# RFID-Reader.net
KiCad netlist of a schematic drawn in Altium Designer
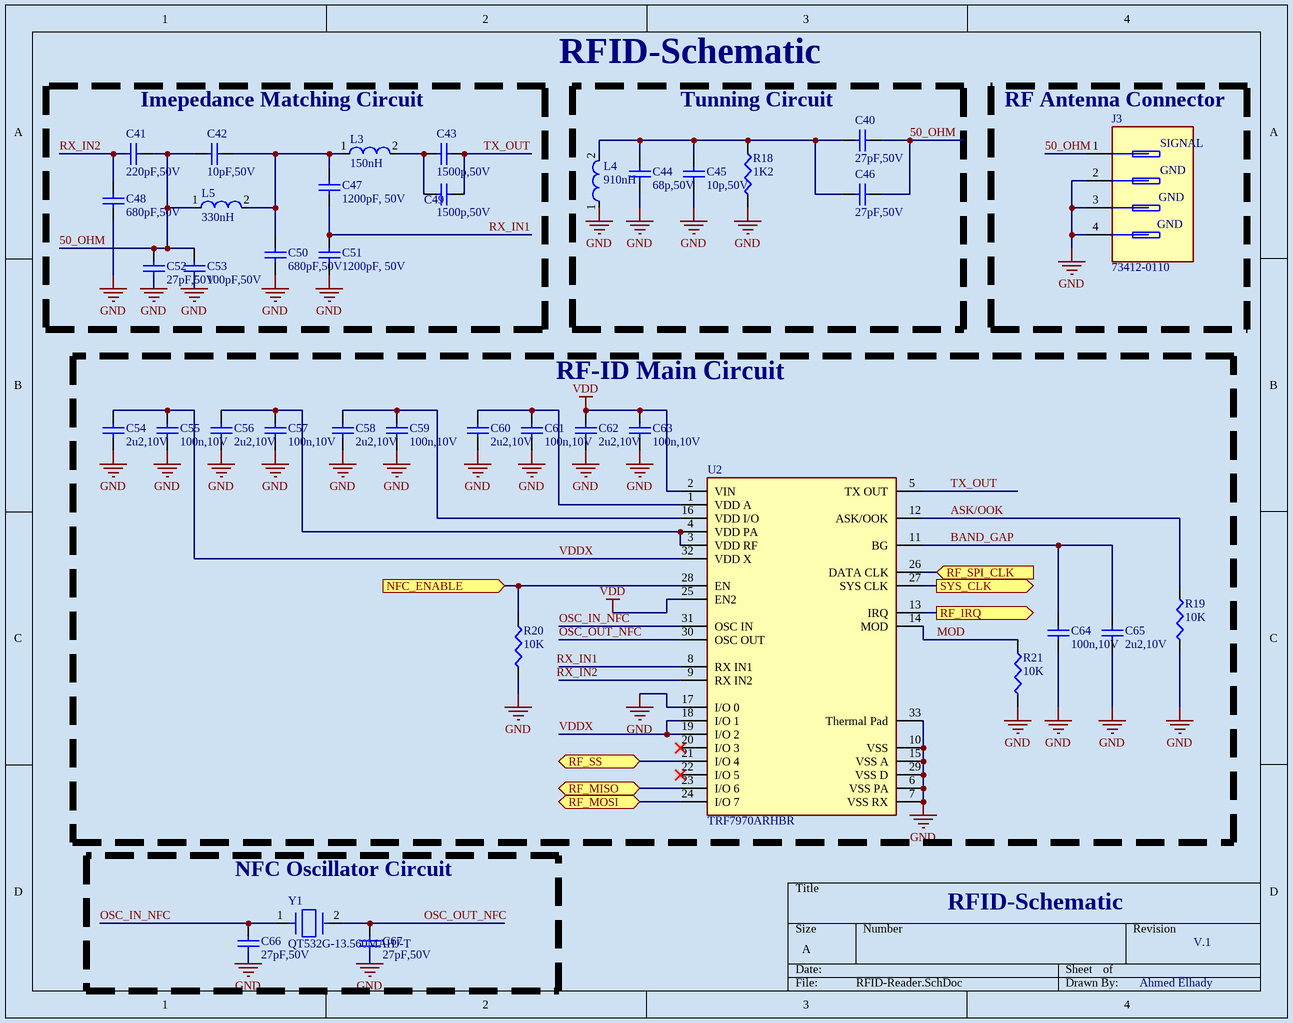
[diagram p0: RFID-Reader.SchDoc]

(export (version "E")
  (design (tool "Eeschema 10.0.6"))
  (components
    (comp (ref "C40")
      (value "27pF,50V")
      (footprint "C0402-27pf-50V")
      (description "27 pF ±5% 50V Ceramic Capacitor C0G, NP0 0402 (1005 Metric)")
      (fields
        (field (name "MANUFACTURER") "Yageo Group")
        (field (name "MANUFACTURER PART NUMBER") "CC0402JRNPO9BN270")
      )
      (libsource (lib "Sch for NFC") (part "CC0402JRNPO9BN270"))
    )
    (comp (ref "C41")
      (value "220pF,50V")
      (footprint "220pf-50v-0402-yageo-CAPC1005X55N")
      (description "220 pF ±5% 25V Ceramic Capacitor C0G, NP0 0402 (1005 Metric)")
      (fields
        (field (name "MANUFACTURER") "Yageo Group")
        (field (name "MANUFACTURER PART NUMBER") "CC0402JRNPO8BN221")
      )
      (libsource (lib "Sch for NFC") (part "CC0402JRNPO8BN221"))
    )
    (comp (ref "C42")
      (value "10pF,50V")
      (footprint "YAGEO_10pf-50v-CC0402JRNPO9BN100_0")
      (description "10 pF ±5% 50V Ceramic Capacitor C0G, NP0 0402 (1005 Metric)")
      (fields
        (field (name "MANUFACTURER") "Yageo Group")
        (field (name "MANUFACTURER PART NUMBER") "CC0402JRNPO9BN100")
      )
      (libsource (lib "Sch for NFC") (part "CC0402JRNPO9BN100"))
    )
    (comp (ref "C43")
      (value "1500p,50V")
      (footprint "C0402-1500pF-Murata_GRM15_MFG")
      (description "1500 pF ±10% 50V Ceramic Capacitor X7R 0402 (1005 Metric)")
      (fields
        (field (name "MANUFACTURER") "Murata")
        (field (name "MANUFACTURER PART NUMBER") "GRM155R71H152KA01D")
      )
      (libsource (lib "Sch for NFC") (part "GRM155R71H152KA01D"))
    )
    (comp (ref "C44")
      (value "68p,50V")
      (footprint "TDK_C1005-68pf-50v")
      (description "68 pF ±5% 50V Ceramic Capacitor C0G, NP0 0402 (1005 Metric)")
      (fields
        (field (name "MANUFACTURER") "TDK")
        (field (name "MANUFACTURER PART NUMBER") "C1005C0G1H680J050BA")
      )
      (libsource (lib "Sch for NFC") (part "C1005C0G1H680J050BA"))
    )
    (comp (ref "C45")
      (value "10p,50V")
      (footprint "YAGEO_10pf-50v-CC0402JRNPO9BN100_0")
      (description "10 pF ±5% 50V Ceramic Capacitor C0G, NP0 0402 (1005 Metric)")
      (fields
        (field (name "MANUFACTURER") "Yageo Group")
        (field (name "MANUFACTURER PART NUMBER") "CC0402JRNPO9BN100")
      )
      (libsource (lib "Sch for NFC") (part "CC0402JRNPO9BN100"))
    )
    (comp (ref "C46")
      (value "27pF,50V")
      (footprint "C0402-27pf-50V")
      (description "27 pF ±5% 50V Ceramic Capacitor C0G, NP0 0402 (1005 Metric)")
      (fields
        (field (name "MANUFACTURER") "Yageo Group")
        (field (name "MANUFACTURER PART NUMBER") "CC0402JRNPO9BN270")
      )
      (libsource (lib "Sch for NFC") (part "CC0402JRNPO9BN270"))
    )
    (comp (ref "C47")
      (value "1200pF, 50V")
      (footprint "1200F-50V-0402-Murata_GRM15_MFG")
      (description "1200 pF ±10% 50V Ceramic Capacitor X7R 0402 (1005 Metric)")
      (fields
        (field (name "MANUFACTURER") "Murata")
        (field (name "MANUFACTURER PART NUMBER") "GRM155R71H122KA01D")
      )
      (libsource (lib "Sch for NFC") (part "GRM155R71H122KA01D"))
    )
    (comp (ref "C48")
      (value "680pF,50V")
      (footprint "Kemet_C0402-680PF-50")
      (description "680 pF ±10% 50V Ceramic Capacitor X7R 0402 (1005 Metric)")
      (fields
        (field (name "MANUFACTURER") "KEMET")
        (field (name "MANUFACTURER PART NUMBER") "C0402C681K5RACTU")
      )
      (libsource (lib "Sch for NFC") (part "C0402C681K5RACTU"))
    )
    (comp (ref "C49")
      (value "1500p,50V")
      (footprint "C0402-1500pF-Murata_GRM15_MFG")
      (description "1500 pF ±10% 50V Ceramic Capacitor X7R 0402 (1005 Metric)")
      (fields
        (field (name "MANUFACTURER") "Murata")
        (field (name "MANUFACTURER PART NUMBER") "GRM155R71H152KA01D")
      )
      (libsource (lib "Sch for NFC") (part "GRM155R71H152KA01D"))
    )
    (comp (ref "C50")
      (value "680pF,50V")
      (footprint "Kemet_C0402-680PF-50")
      (description "680 pF ±10% 50V Ceramic Capacitor X7R 0402 (1005 Metric)")
      (fields
        (field (name "MANUFACTURER") "KEMET")
        (field (name "MANUFACTURER PART NUMBER") "C0402C681K5RACTU")
      )
      (libsource (lib "Sch for NFC") (part "C0402C681K5RACTU"))
    )
    (comp (ref "C51")
      (value "1200pF, 50V")
      (footprint "1200F-50V-0402-Murata_GRM15_MFG")
      (description "1200 pF ±10% 50V Ceramic Capacitor X7R 0402 (1005 Metric)")
      (fields
        (field (name "MANUFACTURER") "Murata")
        (field (name "MANUFACTURER PART NUMBER") "GRM155R71H122KA01D")
      )
      (libsource (lib "Sch for NFC") (part "GRM155R71H122KA01D"))
    )
    (comp (ref "C52")
      (value "27pF,50V")
      (footprint "C0402-27pf-50V")
      (description "27 pF ±5% 50V Ceramic Capacitor C0G, NP0 0402 (1005 Metric)")
      (fields
        (field (name "MANUFACTURER") "Yageo Group")
        (field (name "MANUFACTURER PART NUMBER") "CC0402JRNPO9BN270")
      )
      (libsource (lib "Sch for NFC") (part "CC0402JRNPO9BN270"))
    )
    (comp (ref "C53")
      (value "100pF,50V")
      (footprint "100pf-50v-0402-Murata_GRM15_MFG")
      (description "100 pF ±5% 50V Ceramic Capacitor C0G, NP0 0402 (1005 Metric)")
      (fields
        (field (name "MANUFACTURER") "Murata")
        (field (name "MANUFACTURER PART NUMBER") "GRM1555C1H101JA01D")
      )
      (libsource (lib "Sch for NFC") (part "GRM1555C1H101JA01D"))
    )
    (comp (ref "C54")
      (value "2u2,10V")
      (footprint "C0402-2.2u-10V-Murata_GRM155-0_2_MFG")
      (description "2.2 µF ±10% 10V Ceramic Capacitor X7R 0402 (1005 Metric)")
      (fields
        (field (name "MANUFACTURER") "Murata")
        (field (name "MANUFACTURER PART NUMBER") "GRM155Z71A225KE44D")
      )
      (libsource (lib "Sch for NFC") (part "GRM155Z71A225KE44D"))
    )
    (comp (ref "C55")
      (value "100n,10V")
      (footprint "C0402-100nF-10V")
      (description "0.1 µF ±10% 10V Ceramic Capacitor X7R 0402 (1005 Metric)")
      (fields
        (field (name "MANUFACTURER") "Samsung Electro-Mechanics")
        (field (name "MANUFACTURER PART NUMBER") "CL05B104KP5NNNC")
      )
      (libsource (lib "Sch for NFC") (part "CL05B104KP5NNNC"))
    )
    (comp (ref "C56")
      (value "2u2,10V")
      (footprint "C0402-2.2u-10V-Murata_GRM155-0_2_MFG")
      (description "2.2 µF ±10% 10V Ceramic Capacitor X7R 0402 (1005 Metric)")
      (fields
        (field (name "MANUFACTURER") "Murata")
        (field (name "MANUFACTURER PART NUMBER") "GRM155Z71A225KE44D")
      )
      (libsource (lib "Sch for NFC") (part "GRM155Z71A225KE44D"))
    )
    (comp (ref "C57")
      (value "100n,10V")
      (footprint "C0402-100nF-10V")
      (description "0.1 µF ±10% 10V Ceramic Capacitor X7R 0402 (1005 Metric)")
      (fields
        (field (name "MANUFACTURER") "Samsung Electro-Mechanics")
        (field (name "MANUFACTURER PART NUMBER") "CL05B104KP5NNNC")
      )
      (libsource (lib "Sch for NFC") (part "CL05B104KP5NNNC"))
    )
    (comp (ref "C58")
      (value "2u2,10V")
      (footprint "C0402-2.2u-10V-Murata_GRM155-0_2_MFG")
      (description "2.2 µF ±10% 10V Ceramic Capacitor X7R 0402 (1005 Metric)")
      (fields
        (field (name "MANUFACTURER") "Murata")
        (field (name "MANUFACTURER PART NUMBER") "GRM155Z71A225KE44D")
      )
      (libsource (lib "Sch for NFC") (part "GRM155Z71A225KE44D"))
    )
    (comp (ref "C59")
      (value "100n,10V")
      (footprint "C0402-100nF-10V")
      (description "0.1 µF ±10% 10V Ceramic Capacitor X7R 0402 (1005 Metric)")
      (fields
        (field (name "MANUFACTURER") "Samsung Electro-Mechanics")
        (field (name "MANUFACTURER PART NUMBER") "CL05B104KP5NNNC")
      )
      (libsource (lib "Sch for NFC") (part "CL05B104KP5NNNC"))
    )
    (comp (ref "C60")
      (value "2u2,10V")
      (footprint "C0402-2.2u-10V-Murata_GRM155-0_2_MFG")
      (description "2.2 µF ±10% 10V Ceramic Capacitor X7R 0402 (1005 Metric)")
      (fields
        (field (name "MANUFACTURER") "Murata")
        (field (name "MANUFACTURER PART NUMBER") "GRM155Z71A225KE44D")
      )
      (libsource (lib "Sch for NFC") (part "GRM155Z71A225KE44D"))
    )
    (comp (ref "C61")
      (value "100n,10V")
      (footprint "C0402-100nF-10V")
      (description "0.1 µF ±10% 10V Ceramic Capacitor X7R 0402 (1005 Metric)")
      (fields
        (field (name "MANUFACTURER") "Samsung Electro-Mechanics")
        (field (name "MANUFACTURER PART NUMBER") "CL05B104KP5NNNC")
      )
      (libsource (lib "Sch for NFC") (part "CL05B104KP5NNNC"))
    )
    (comp (ref "C62")
      (value "2u2,10V")
      (footprint "C0402-2.2u-10V-Murata_GRM155-0_2_MFG")
      (description "2.2 µF ±10% 10V Ceramic Capacitor X7R 0402 (1005 Metric)")
      (fields
        (field (name "MANUFACTURER") "Murata")
        (field (name "MANUFACTURER PART NUMBER") "GRM155Z71A225KE44D")
      )
      (libsource (lib "Sch for NFC") (part "GRM155Z71A225KE44D"))
    )
    (comp (ref "C63")
      (value "100n,10V")
      (footprint "C0402-100nF-10V")
      (description "0.1 µF ±10% 10V Ceramic Capacitor X7R 0402 (1005 Metric)")
      (fields
        (field (name "MANUFACTURER") "Samsung Electro-Mechanics")
        (field (name "MANUFACTURER PART NUMBER") "CL05B104KP5NNNC")
      )
      (libsource (lib "Sch for NFC") (part "CL05B104KP5NNNC"))
    )
    (comp (ref "C64")
      (value "100n,10V")
      (footprint "C0402-100nF-10V")
      (description "0.1 µF ±10% 10V Ceramic Capacitor X7R 0402 (1005 Metric)")
      (fields
        (field (name "MANUFACTURER") "Samsung Electro-Mechanics")
        (field (name "MANUFACTURER PART NUMBER") "CL05B104KP5NNNC")
      )
      (libsource (lib "Sch for NFC") (part "CL05B104KP5NNNC"))
    )
    (comp (ref "C65")
      (value "2u2,10V")
      (footprint "C0402-2.2u-10V-Murata_GRM155-0_2_MFG")
      (description "2.2 µF ±10% 10V Ceramic Capacitor X7R 0402 (1005 Metric)")
      (fields
        (field (name "MANUFACTURER") "Murata")
        (field (name "MANUFACTURER PART NUMBER") "GRM155Z71A225KE44D")
      )
      (libsource (lib "Sch for NFC") (part "GRM155Z71A225KE44D"))
    )
    (comp (ref "C66")
      (value "27pF,50V")
      (footprint "C0402-27pf-50V")
      (description "27 pF ±5% 50V Ceramic Capacitor C0G, NP0 0402 (1005 Metric)")
      (fields
        (field (name "MANUFACTURER") "Yageo Group")
        (field (name "MANUFACTURER PART NUMBER") "CC0402JRNPO9BN270")
      )
      (libsource (lib "Sch for NFC") (part "CC0402JRNPO9BN270"))
    )
    (comp (ref "C67")
      (value "27pF,50V")
      (footprint "C0402-27pf-50V")
      (description "27 pF ±5% 50V Ceramic Capacitor C0G, NP0 0402 (1005 Metric)")
      (fields
        (field (name "MANUFACTURER") "Yageo Group")
        (field (name "MANUFACTURER PART NUMBER") "CC0402JRNPO9BN270")
      )
      (libsource (lib "Sch for NFC") (part "CC0402JRNPO9BN270"))
    )
    (comp (ref "J3")
      (value "73412-0110")
      (footprint "ANT_CONN_Molex_734-12-0110_0")
      (description "U.FL (UMCC) ANTENNA Connector Receptacle, Male Pin 50 Ohms Surface Mount Solder")
      (fields (field (name "MANUFACTURER") "Molex"))
      (libsource (lib "Sch for NFC") (part "73412-0110"))
    )
    (comp (ref "L3")
      (value "150nH")
      (footprint "150nH-SMD2")
      (description "150 nH Unshielded Drum Core, Wirewound Inductor 800 mA 220mOhm Max 1008 (2520 Metric)")
      (fields
        (field (name "MANUFACTURER") "Wurth Elektronik")
        (field (name "MANUFACTURER PART NUMBER") "744762215A")
      )
      (libsource (lib "Sch for NFC") (part "744762215A"))
    )
    (comp (ref "L4")
      (value "910nH")
      (footprint "COIL_910nH_SMD")
      (description "910 nH Unshielded Drum Core, Wirewound Inductor 380 mA 1.68Ohm Max 1008 (2520 Metric)")
      (fields
        (field (name "MANUFACTURER") "Pulse Electronics")
        (field (name "MANUFACTURER PART NUMBER") "BWCS00292821R91J00")
      )
      (libsource (lib "Sch for NFC") (part "BWCS00292821R91J00"))
    )
    (comp (ref "L5")
      (value "330nH")
      (footprint "330nh-SMD2")
      (description "330 nH Unshielded Drum Core, Wirewound Inductor 500 mA 900mOhm Max 1008 (2520 Metric)")
      (fields
        (field (name "MANUFACTURER") "Wurth Elektronik")
        (field (name "MANUFACTURER PART NUMBER") "744762233A")
      )
      (libsource (lib "Sch for NFC") (part "744762233A"))
    )
    (comp (ref "R18")
      (value "1K2")
      (footprint "RESC1005X40N-1.2k")
      (description "1.2 kOhms ±5% 0.063W, 1/16W Chip Resistor 0402 (1005 Metric) Moisture Resistant Thick Film")
      (fields
        (field (name "MANUFACTURER") "Yageo Group")
        (field (name "MANUFACTURER PART NUMBER") "RC0402JR-071K2L")
      )
      (libsource (lib "Sch for NFC") (part "RC0402JR-071K2L"))
    )
    (comp (ref "R19")
      (value "10K")
      (footprint "YAGEO-0603-10K-0.1W")
      (description "10 kOhms ±1% 0.1W, 1/10W Chip Resistor 0603 (1608 Metric) Moisture Resistant Thick Film")
      (fields
        (field (name "MANUFACTURER") "Yageo Group")
        (field (name "MANUFACTURER PART NUMBER") "RC0603FR-0710KL")
      )
      (libsource (lib "Sch for NFC") (part "RC0603FR-0710KL"))
    )
    (comp (ref "R20")
      (value "10K")
      (footprint "YAGEO-0603-10K-0.1W")
      (description "10 kOhms ±1% 0.1W, 1/10W Chip Resistor 0603 (1608 Metric) Moisture Resistant Thick Film")
      (fields
        (field (name "MANUFACTURER") "Yageo Group")
        (field (name "MANUFACTURER PART NUMBER") "RC0603FR-0710KL")
      )
      (libsource (lib "Sch for NFC") (part "RC0603FR-0710KL"))
    )
    (comp (ref "R21")
      (value "10K")
      (footprint "YAGEO-0603-10K-0.1W")
      (description "10 kOhms ±1% 0.1W, 1/10W Chip Resistor 0603 (1608 Metric) Moisture Resistant Thick Film")
      (fields
        (field (name "MANUFACTURER") "Yageo Group")
        (field (name "MANUFACTURER PART NUMBER") "RC0603FR-0710KL")
      )
      (libsource (lib "Sch for NFC") (part "RC0603FR-0710KL"))
    )
    (comp (ref "U2")
      (value "TRF7970ARHBR")
      (footprint "NFC_FP_TRF7970ARHBR")
      (fields (field (name "MANUFACTURER") "Texas Instruments"))
      (libsource (lib "Sch for NFC") (part "TRF7970ARHBR"))
    )
    (comp (ref "Y1")
      (value "QT532G-13.560MAHJ-T")
      (footprint "Crystal-13.56 MHz")
      (description "13.56 MHz ±30ppm Crystal 18pF 50 Ohms 2-SMD, No Lead")
      (fields (field (name "MANUFACTURER") "QST"))
      (libsource (lib "Sch for NFC") (part "QT532G-13.560MAHJ-T"))
    )
  )
  (nets
    (net (code "1") (name "/50_OHM") (class "Default")
      (node (ref "C40") (pin "2") (pinfunction "2_2") (pintype "passive"))
      (node (ref "C41") (pin "1") (pinfunction "1_1") (pintype "passive"))
      (node (ref "C42") (pin "1") (pinfunction "1_1") (pintype "passive"))
      (node (ref "C46") (pin "2") (pinfunction "2_2") (pintype "passive"))
      (node (ref "C52") (pin "2") (pinfunction "2_2") (pintype "passive"))
      (node (ref "C53") (pin "2") (pinfunction "2_2") (pintype "passive"))
      (node (ref "J3") (pin "1") (pinfunction "SIGNAL_1") (pintype "passive"))
      (node (ref "L5") (pin "1") (pinfunction "1_1") (pintype "passive"))
    )
    (net (code "2") (name "/ASK{slash}OOK") (class "Default")
      (node (ref "R19") (pin "2") (pinfunction "2_2") (pintype "passive"))
      (node (ref "U2") (pin "12") (pinfunction "ASK/OOK_12") (pintype "passive"))
    )
    (net (code "3") (name "/BAND_GAP") (class "Default")
      (node (ref "C64") (pin "2") (pinfunction "2_2") (pintype "passive"))
      (node (ref "C65") (pin "2") (pinfunction "2_2") (pintype "passive"))
      (node (ref "U2") (pin "11") (pinfunction "BG_11") (pintype "passive"))
    )
    (net (code "4") (name "/MOD") (class "Default")
      (node (ref "R21") (pin "2") (pinfunction "2_2") (pintype "passive"))
      (node (ref "U2") (pin "14") (pinfunction "MOD_14") (pintype "passive"))
    )
    (net (code "5") (name "/NFC_ENABLE") (class "Default")
      (node (ref "R20") (pin "2") (pinfunction "2_2") (pintype "passive"))
      (node (ref "U2") (pin "28") (pinfunction "EN_28") (pintype "passive"))
    )
    (net (code "6") (name "/OSC_IN_NFC") (class "Default")
      (node (ref "C66") (pin "2") (pinfunction "2_2") (pintype "passive"))
      (node (ref "U2") (pin "31") (pinfunction "OSC_IN_31") (pintype "passive"))
      (node (ref "Y1") (pin "1") (pinfunction "1_1") (pintype "passive"))
    )
    (net (code "7") (name "/OSC_OUT_NFC") (class "Default")
      (node (ref "C67") (pin "2") (pinfunction "2_2") (pintype "passive"))
      (node (ref "U2") (pin "30") (pinfunction "OSC_OUT_30") (pintype "passive"))
      (node (ref "Y1") (pin "2") (pinfunction "2_2") (pintype "passive"))
    )
    (net (code "8") (name "/RF_IRQ") (class "Default")
      (node (ref "U2") (pin "13") (pinfunction "IRQ_13") (pintype "passive"))
    )
    (net (code "9") (name "/RF_MISO") (class "Default")
      (node (ref "U2") (pin "23") (pinfunction "I/O_6_23") (pintype "passive"))
    )
    (net (code "10") (name "/RF_MOSI") (class "Default")
      (node (ref "U2") (pin "24") (pinfunction "I/O_7_24") (pintype "passive"))
    )
    (net (code "11") (name "/RF_SPI_CLK") (class "Default")
      (node (ref "U2") (pin "26") (pinfunction "DATA_CLK_26") (pintype "passive"))
    )
    (net (code "12") (name "/RF_SS") (class "Default")
      (node (ref "U2") (pin "21") (pinfunction "I/O_4_21") (pintype "passive"))
    )
    (net (code "13") (name "/RX_IN1") (class "Default")
      (node (ref "C47") (pin "1") (pinfunction "1_1") (pintype "passive"))
      (node (ref "C51") (pin "2") (pinfunction "2_2") (pintype "passive"))
      (node (ref "U2") (pin "8") (pinfunction "RX_IN1_8") (pintype "passive"))
    )
    (net (code "14") (name "/RX_IN2") (class "Default")
      (node (ref "C41") (pin "2") (pinfunction "2_2") (pintype "passive"))
      (node (ref "C48") (pin "2") (pinfunction "2_2") (pintype "passive"))
      (node (ref "U2") (pin "9") (pinfunction "RX_IN2_9") (pintype "passive"))
    )
    (net (code "15") (name "/SYS_CLK") (class "Default")
      (node (ref "U2") (pin "27") (pinfunction "SYS_CLK_27") (pintype "passive"))
    )
    (net (code "16") (name "/TX_OUT") (class "Default")
      (node (ref "C43") (pin "2") (pinfunction "2_2") (pintype "passive"))
      (node (ref "C49") (pin "2") (pinfunction "2_2") (pintype "passive"))
      (node (ref "U2") (pin "5") (pinfunction "TX_OUT_5") (pintype "passive"))
    )
    (net (code "17") (name "/VDDX") (class "Default")
      (node (ref "C54") (pin "2") (pinfunction "2_2") (pintype "passive"))
      (node (ref "C55") (pin "2") (pinfunction "2_2") (pintype "passive"))
      (node (ref "U2") (pin "18") (pinfunction "I/O_1_18") (pintype "passive"))
      (node (ref "U2") (pin "19") (pinfunction "I/O_2_19") (pintype "passive"))
      (node (ref "U2") (pin "32") (pinfunction "VDD_X_32") (pintype "passive"))
    )
    (net (code "18") (name "GND") (class "Default")
      (node (ref "C44") (pin "1") (pinfunction "1_1") (pintype "passive"))
      (node (ref "C45") (pin "2") (pinfunction "2_2") (pintype "passive"))
      (node (ref "C48") (pin "1") (pinfunction "1_1") (pintype "passive"))
      (node (ref "C50") (pin "1") (pinfunction "1_1") (pintype "passive"))
      (node (ref "C51") (pin "1") (pinfunction "1_1") (pintype "passive"))
      (node (ref "C52") (pin "1") (pinfunction "1_1") (pintype "passive"))
      (node (ref "C53") (pin "1") (pinfunction "1_1") (pintype "passive"))
      (node (ref "C54") (pin "1") (pinfunction "1_1") (pintype "passive"))
      (node (ref "C55") (pin "1") (pinfunction "1_1") (pintype "passive"))
      (node (ref "C56") (pin "1") (pinfunction "1_1") (pintype "passive"))
      (node (ref "C57") (pin "1") (pinfunction "1_1") (pintype "passive"))
      (node (ref "C58") (pin "1") (pinfunction "1_1") (pintype "passive"))
      (node (ref "C59") (pin "1") (pinfunction "1_1") (pintype "passive"))
      (node (ref "C60") (pin "1") (pinfunction "1_1") (pintype "passive"))
      (node (ref "C61") (pin "1") (pinfunction "1_1") (pintype "passive"))
      (node (ref "C62") (pin "1") (pinfunction "1_1") (pintype "passive"))
      (node (ref "C63") (pin "1") (pinfunction "1_1") (pintype "passive"))
      (node (ref "C64") (pin "1") (pinfunction "1_1") (pintype "passive"))
      (node (ref "C65") (pin "1") (pinfunction "1_1") (pintype "passive"))
      (node (ref "C66") (pin "1") (pinfunction "1_1") (pintype "passive"))
      (node (ref "C67") (pin "1") (pinfunction "1_1") (pintype "passive"))
      (node (ref "J3") (pin "2") (pinfunction "GROUND_2") (pintype "passive"))
      (node (ref "J3") (pin "3") (pinfunction "GROUND_3") (pintype "passive"))
      (node (ref "J3") (pin "4") (pinfunction "GROUND_4") (pintype "passive"))
      (node (ref "L4") (pin "1") (pinfunction "1_1") (pintype "passive"))
      (node (ref "R18") (pin "1") (pinfunction "1_1") (pintype "passive"))
      (node (ref "R19") (pin "1") (pinfunction "1_1") (pintype "passive"))
      (node (ref "R20") (pin "1") (pinfunction "1_1") (pintype "passive"))
      (node (ref "R21") (pin "1") (pinfunction "1_1") (pintype "passive"))
      (node (ref "U2") (pin "10") (pinfunction "VSS_10") (pintype "passive"))
      (node (ref "U2") (pin "15") (pinfunction "VSS_A_15") (pintype "passive"))
      (node (ref "U2") (pin "17") (pinfunction "I/O_0_17") (pintype "passive"))
      (node (ref "U2") (pin "29") (pinfunction "VSS_D_29") (pintype "passive"))
      (node (ref "U2") (pin "33") (pinfunction "Thermal_Pad_33") (pintype "passive"))
      (node (ref "U2") (pin "6") (pinfunction "VSS_PA_6") (pintype "passive"))
      (node (ref "U2") (pin "7") (pinfunction "VSS_RX_7") (pintype "passive"))
    )
    (net (code "19") (name "Net-(C40-Pad1)") (class "Default")
      (node (ref "C40") (pin "1") (pinfunction "1_1") (pintype "passive"))
      (node (ref "C44") (pin "2") (pinfunction "2_2") (pintype "passive"))
      (node (ref "C45") (pin "1") (pinfunction "1_1") (pintype "passive"))
      (node (ref "C46") (pin "1") (pinfunction "1_1") (pintype "passive"))
      (node (ref "L4") (pin "2") (pinfunction "2_2") (pintype "passive"))
      (node (ref "R18") (pin "2") (pinfunction "2_2") (pintype "passive"))
    )
    (net (code "20") (name "Net-(C42-Pad2)") (class "Default")
      (node (ref "C42") (pin "2") (pinfunction "2_2") (pintype "passive"))
      (node (ref "C47") (pin "2") (pinfunction "2_2") (pintype "passive"))
      (node (ref "C50") (pin "2") (pinfunction "2_2") (pintype "passive"))
      (node (ref "L3") (pin "1") (pinfunction "1_1") (pintype "passive"))
      (node (ref "L5") (pin "2") (pinfunction "2_2") (pintype "passive"))
    )
    (net (code "21") (name "Net-(C43-Pad1)") (class "Default")
      (node (ref "C43") (pin "1") (pinfunction "1_1") (pintype "passive"))
      (node (ref "C49") (pin "1") (pinfunction "1_1") (pintype "passive"))
      (node (ref "L3") (pin "2") (pinfunction "2_2") (pintype "passive"))
    )
    (net (code "22") (name "Net-(U2-VDD_A)") (class "Default")
      (node (ref "C60") (pin "2") (pinfunction "2_2") (pintype "passive"))
      (node (ref "C61") (pin "2") (pinfunction "2_2") (pintype "passive"))
      (node (ref "U2") (pin "1") (pinfunction "VDD_A_1") (pintype "passive"))
    )
    (net (code "23") (name "Net-(U2-VDD_I{slash}O)") (class "Default")
      (node (ref "C58") (pin "2") (pinfunction "2_2") (pintype "passive"))
      (node (ref "C59") (pin "2") (pinfunction "2_2") (pintype "passive"))
      (node (ref "U2") (pin "16") (pinfunction "VDD_I/O_16") (pintype "passive"))
    )
    (net (code "24") (name "Net-(U2-VDD_PA)") (class "Default")
      (node (ref "C56") (pin "2") (pinfunction "2_2") (pintype "passive"))
      (node (ref "C57") (pin "2") (pinfunction "2_2") (pintype "passive"))
      (node (ref "U2") (pin "3") (pinfunction "VDD_RF_3") (pintype "passive"))
      (node (ref "U2") (pin "4") (pinfunction "VDD_PA_4") (pintype "passive"))
    )
    (net (code "25") (name "VDD") (class "Default")
      (node (ref "C62") (pin "2") (pinfunction "2_2") (pintype "passive"))
      (node (ref "C63") (pin "2") (pinfunction "2_2") (pintype "passive"))
      (node (ref "U2") (pin "2") (pinfunction "VIN_2") (pintype "passive"))
      (node (ref "U2") (pin "25") (pinfunction "EN2_25") (pintype "passive"))
    )
    (net (code "26") (name "unconnected-(U2-I{slash}O_3-Pad20)") (class "Default")
      (node (ref "U2") (pin "20") (pinfunction "I/O_3_20") (pintype "passive+no_connect"))
    )
    (net (code "27") (name "unconnected-(U2-I{slash}O_5-Pad22)") (class "Default")
      (node (ref "U2") (pin "22") (pinfunction "I/O_5_22") (pintype "passive+no_connect"))
    )
  )
)
